# rtpi.net
KiCad netlist of a schematic drawn in Altium Designer
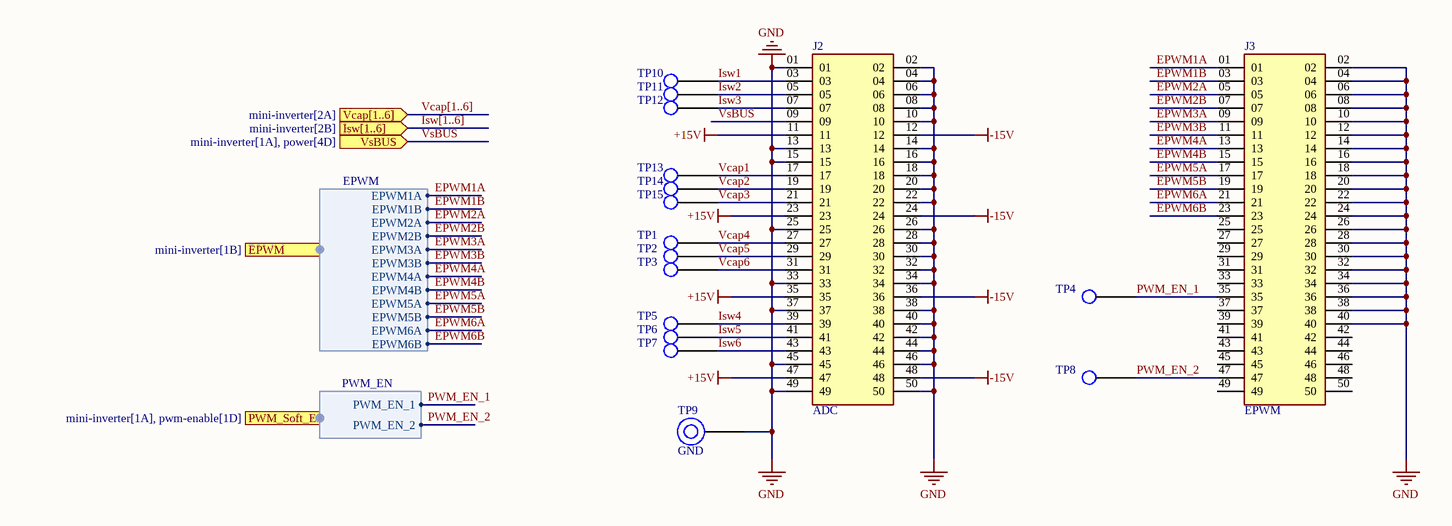
[diagram p0: rtpi.SchDoc]

(export (version "E")
  (design (tool "Eeschema 10.0.6"))
  (components
    (comp (ref "J2")
      (value "ADC")
      (footprint "SHF-125-01-L-D-RA")
      (description "50-Pin Simplus Connector")
      (fields (field (name "MP") "SHF-125-01-L-D-RA") (field (name "MF") "Samtec"))
      (libsource (lib "FYP_Components") (part "SHF-125-01-L-D-RA"))
    )
    (comp (ref "J3")
      (value "EPWM")
      (footprint "SHF-125-01-L-D-RA")
      (description "50-Pin Simplus Connector")
      (fields (field (name "MP") "SHF-125-01-L-D-RA") (field (name "MF") "Samtec"))
      (libsource (lib "FYP_Components") (part "SHF-125-01-L-D-RA"))
    )
    (comp (ref "TP1")
      (value "VC_1A")
      (footprint "PCB 1.32mm TestPoint")
      (description "20-313143 PCB Test Point, White, Through Hole Mount, 1.32 mm, Phosphor Bronze, Tin Plated Contacts")
      (libsource (lib "FYP_Components") (part "PCBTestpoint"))
    )
    (comp (ref "TP2")
      (value "VC_1B")
      (footprint "PCB 1.32mm TestPoint")
      (description "20-313143 PCB Test Point, White, Through Hole Mount, 1.32 mm, Phosphor Bronze, Tin Plated Contacts")
      (libsource (lib "FYP_Components") (part "PCBTestpoint"))
    )
    (comp (ref "TP3")
      (value "VC_1C")
      (footprint "PCB 1.32mm TestPoint")
      (description "20-313143 PCB Test Point, White, Through Hole Mount, 1.32 mm, Phosphor Bronze, Tin Plated Contacts")
      (libsource (lib "FYP_Components") (part "PCBTestpoint"))
    )
    (comp (ref "TP4")
      (value "PWMEN1")
      (footprint "PCB 1.32mm TestPoint")
      (description "20-313143 PCB Test Point, White, Through Hole Mount, 1.32 mm, Phosphor Bronze, Tin Plated Contacts")
      (libsource (lib "FYP_Components") (part "PCBTestpoint"))
    )
    (comp (ref "TP5")
      (value "I1")
      (footprint "PCB 1.32mm TestPoint")
      (description "20-313143 PCB Test Point, White, Through Hole Mount, 1.32 mm, Phosphor Bronze, Tin Plated Contacts")
      (libsource (lib "FYP_Components") (part "PCBTestpoint"))
    )
    (comp (ref "TP6")
      (value "I2")
      (footprint "PCB 1.32mm TestPoint")
      (description "20-313143 PCB Test Point, White, Through Hole Mount, 1.32 mm, Phosphor Bronze, Tin Plated Contacts")
      (libsource (lib "FYP_Components") (part "PCBTestpoint"))
    )
    (comp (ref "TP7")
      (value "I3")
      (footprint "PCB 1.32mm TestPoint")
      (description "20-313143 PCB Test Point, White, Through Hole Mount, 1.32 mm, Phosphor Bronze, Tin Plated Contacts")
      (libsource (lib "FYP_Components") (part "PCBTestpoint"))
    )
    (comp (ref "TP8")
      (value "PWMEN2")
      (footprint "PCB 1.32mm TestPoint")
      (description "20-313143 PCB Test Point, White, Through Hole Mount, 1.32 mm, Phosphor Bronze, Tin Plated Contacts")
      (libsource (lib "FYP_Components") (part "PCBTestpoint"))
    )
    (comp (ref "TP9")
      (value "GND")
      (footprint "1.9mm Hole")
      (description "H2182-01 PCB Test Point, PCB Mount, 1.9 mm, Brass, Tin Plated Contacts")
      (libsource (lib "FYP_Components") (part "GroundTestPoint"))
    )
    (comp (ref "TP10")
      (value "VC_1A")
      (footprint "PCB 1.32mm TestPoint")
      (description "20-313143 PCB Test Point, White, Through Hole Mount, 1.32 mm, Phosphor Bronze, Tin Plated Contacts")
      (libsource (lib "FYP_Components") (part "PCBTestpoint"))
    )
    (comp (ref "TP11")
      (value "VC_1B")
      (footprint "PCB 1.32mm TestPoint")
      (description "20-313143 PCB Test Point, White, Through Hole Mount, 1.32 mm, Phosphor Bronze, Tin Plated Contacts")
      (libsource (lib "FYP_Components") (part "PCBTestpoint"))
    )
    (comp (ref "TP12")
      (value "VC_1C")
      (footprint "PCB 1.32mm TestPoint")
      (description "20-313143 PCB Test Point, White, Through Hole Mount, 1.32 mm, Phosphor Bronze, Tin Plated Contacts")
      (libsource (lib "FYP_Components") (part "PCBTestpoint"))
    )
    (comp (ref "TP13")
      (value "VC_1A")
      (footprint "PCB 1.32mm TestPoint")
      (description "20-313143 PCB Test Point, White, Through Hole Mount, 1.32 mm, Phosphor Bronze, Tin Plated Contacts")
      (libsource (lib "FYP_Components") (part "PCBTestpoint"))
    )
    (comp (ref "TP14")
      (value "VC_1B")
      (footprint "PCB 1.32mm TestPoint")
      (description "20-313143 PCB Test Point, White, Through Hole Mount, 1.32 mm, Phosphor Bronze, Tin Plated Contacts")
      (libsource (lib "FYP_Components") (part "PCBTestpoint"))
    )
    (comp (ref "TP15")
      (value "VC_1C")
      (footprint "PCB 1.32mm TestPoint")
      (description "20-313143 PCB Test Point, White, Through Hole Mount, 1.32 mm, Phosphor Bronze, Tin Plated Contacts")
      (libsource (lib "FYP_Components") (part "PCBTestpoint"))
    )
  )
  (nets
    (net (code "3") (name "+15V") (class "Default")
      (node (ref "J2") (pin "11") (pinfunction "11_11") (pintype "passive"))
      (node (ref "J2") (pin "23") (pinfunction "23_23") (pintype "passive"))
      (node (ref "J2") (pin "35") (pinfunction "35_35") (pintype "passive"))
      (node (ref "J2") (pin "47") (pinfunction "47_47") (pintype "passive"))
    )
    (net (code "4") (name "-15V") (class "Default")
      (node (ref "J2") (pin "12") (pinfunction "12_12") (pintype "passive"))
      (node (ref "J2") (pin "24") (pinfunction "24_24") (pintype "passive"))
      (node (ref "J2") (pin "36") (pinfunction "36_36") (pintype "passive"))
      (node (ref "J2") (pin "48") (pinfunction "48_48") (pintype "passive"))
    )
    (net (code "5") (name "/EPWM1A") (class "Default")
      (node (ref "J3") (pin "01") (pinfunction "01_01") (pintype "passive"))
    )
    (net (code "6") (name "/EPWM1B") (class "Default")
      (node (ref "J3") (pin "03") (pinfunction "03_03") (pintype "passive"))
    )
    (net (code "7") (name "/EPWM2A") (class "Default")
      (node (ref "J3") (pin "05") (pinfunction "05_05") (pintype "passive"))
    )
    (net (code "8") (name "/EPWM2B") (class "Default")
      (node (ref "J3") (pin "07") (pinfunction "07_07") (pintype "passive"))
    )
    (net (code "9") (name "/EPWM3A") (class "Default")
      (node (ref "J3") (pin "09") (pinfunction "09_09") (pintype "passive"))
    )
    (net (code "10") (name "/EPWM3B") (class "Default")
      (node (ref "J3") (pin "11") (pinfunction "11_11") (pintype "passive"))
    )
    (net (code "11") (name "/EPWM4A") (class "Default")
      (node (ref "J3") (pin "13") (pinfunction "13_13") (pintype "passive"))
    )
    (net (code "12") (name "/EPWM4B") (class "Default")
      (node (ref "J3") (pin "15") (pinfunction "15_15") (pintype "passive"))
    )
    (net (code "13") (name "/EPWM5A") (class "Default")
      (node (ref "J3") (pin "17") (pinfunction "17_17") (pintype "passive"))
    )
    (net (code "14") (name "/EPWM5B") (class "Default")
      (node (ref "J3") (pin "19") (pinfunction "19_19") (pintype "passive"))
    )
    (net (code "15") (name "/EPWM6A") (class "Default")
      (node (ref "J3") (pin "21") (pinfunction "21_21") (pintype "passive"))
    )
    (net (code "16") (name "/EPWM6B") (class "Default")
      (node (ref "J3") (pin "23") (pinfunction "23_23") (pintype "passive"))
    )
    (net (code "17") (name "/Isw1") (class "Default")
      (node (ref "J2") (pin "03") (pinfunction "03_03") (pintype "passive"))
      (node (ref "TP10") (pin "1") (pinfunction "1_1") (pintype "passive"))
    )
    (net (code "18") (name "/Isw2") (class "Default")
      (node (ref "J2") (pin "05") (pinfunction "05_05") (pintype "passive"))
      (node (ref "TP11") (pin "1") (pinfunction "1_1") (pintype "passive"))
    )
    (net (code "19") (name "/Isw3") (class "Default")
      (node (ref "J2") (pin "07") (pinfunction "07_07") (pintype "passive"))
      (node (ref "TP12") (pin "1") (pinfunction "1_1") (pintype "passive"))
    )
    (net (code "20") (name "/Isw4") (class "Default")
      (node (ref "J2") (pin "39") (pinfunction "39_39") (pintype "passive"))
      (node (ref "TP5") (pin "1") (pinfunction "1_1") (pintype "passive"))
    )
    (net (code "21") (name "/Isw5") (class "Default")
      (node (ref "J2") (pin "41") (pinfunction "41_41") (pintype "passive"))
      (node (ref "TP6") (pin "1") (pinfunction "1_1") (pintype "passive"))
    )
    (net (code "22") (name "/Isw6") (class "Default")
      (node (ref "J2") (pin "43") (pinfunction "43_43") (pintype "passive"))
      (node (ref "TP7") (pin "1") (pinfunction "1_1") (pintype "passive"))
    )
    (net (code "24") (name "/PWM_EN_1") (class "Default")
      (node (ref "J3") (pin "35") (pinfunction "35_35") (pintype "passive"))
      (node (ref "TP4") (pin "1") (pinfunction "1_1") (pintype "passive"))
    )
    (net (code "25") (name "/PWM_EN_2") (class "Default")
      (node (ref "J3") (pin "47") (pinfunction "47_47") (pintype "passive"))
      (node (ref "TP8") (pin "1") (pinfunction "1_1") (pintype "passive"))
    )
    (net (code "26") (name "/Vcap1") (class "Default")
      (node (ref "J2") (pin "17") (pinfunction "17_17") (pintype "passive"))
      (node (ref "TP13") (pin "1") (pinfunction "1_1") (pintype "passive"))
    )
    (net (code "27") (name "/Vcap2") (class "Default")
      (node (ref "J2") (pin "19") (pinfunction "19_19") (pintype "passive"))
      (node (ref "TP14") (pin "1") (pinfunction "1_1") (pintype "passive"))
    )
    (net (code "28") (name "/Vcap3") (class "Default")
      (node (ref "J2") (pin "21") (pinfunction "21_21") (pintype "passive"))
      (node (ref "TP15") (pin "1") (pinfunction "1_1") (pintype "passive"))
    )
    (net (code "29") (name "/Vcap4") (class "Default")
      (node (ref "J2") (pin "27") (pinfunction "27_27") (pintype "passive"))
      (node (ref "TP1") (pin "1") (pinfunction "1_1") (pintype "passive"))
    )
    (net (code "30") (name "/Vcap5") (class "Default")
      (node (ref "J2") (pin "29") (pinfunction "29_29") (pintype "passive"))
      (node (ref "TP2") (pin "1") (pinfunction "1_1") (pintype "passive"))
    )
    (net (code "31") (name "/Vcap6") (class "Default")
      (node (ref "J2") (pin "31") (pinfunction "31_31") (pintype "passive"))
      (node (ref "TP3") (pin "1") (pinfunction "1_1") (pintype "passive"))
    )
    (net (code "33") (name "/VsBUS") (class "Default")
      (node (ref "J2") (pin "09") (pinfunction "09_09") (pintype "passive"))
    )
    (net (code "36") (name "GND") (class "Default")
      (node (ref "J2") (pin "01") (pinfunction "01_01") (pintype "passive"))
      (node (ref "J2") (pin "02") (pinfunction "02_02") (pintype "passive"))
      (node (ref "J2") (pin "04") (pinfunction "04_04") (pintype "passive"))
      (node (ref "J2") (pin "06") (pinfunction "06_06") (pintype "passive"))
      (node (ref "J2") (pin "08") (pinfunction "08_08") (pintype "passive"))
      (node (ref "J2") (pin "10") (pinfunction "10_10") (pintype "passive"))
      (node (ref "J2") (pin "13") (pinfunction "13_13") (pintype "passive"))
      (node (ref "J2") (pin "14") (pinfunction "14_14") (pintype "passive"))
      (node (ref "J2") (pin "15") (pinfunction "15_15") (pintype "passive"))
      (node (ref "J2") (pin "16") (pinfunction "16_16") (pintype "passive"))
      (node (ref "J2") (pin "18") (pinfunction "18_18") (pintype "passive"))
      (node (ref "J2") (pin "20") (pinfunction "20_20") (pintype "passive"))
      (node (ref "J2") (pin "22") (pinfunction "22_22") (pintype "passive"))
      (node (ref "J2") (pin "25") (pinfunction "25_25") (pintype "passive"))
      (node (ref "J2") (pin "26") (pinfunction "26_26") (pintype "passive"))
      (node (ref "J2") (pin "28") (pinfunction "28_28") (pintype "passive"))
      (node (ref "J2") (pin "30") (pinfunction "30_30") (pintype "passive"))
      (node (ref "J2") (pin "32") (pinfunction "32_32") (pintype "passive"))
      (node (ref "J2") (pin "33") (pinfunction "33_33") (pintype "passive"))
      (node (ref "J2") (pin "34") (pinfunction "34_34") (pintype "passive"))
      (node (ref "J2") (pin "37") (pinfunction "37_37") (pintype "passive"))
      (node (ref "J2") (pin "38") (pinfunction "38_38") (pintype "passive"))
      (node (ref "J2") (pin "40") (pinfunction "40_40") (pintype "passive"))
      (node (ref "J2") (pin "42") (pinfunction "42_42") (pintype "passive"))
      (node (ref "J2") (pin "44") (pinfunction "44_44") (pintype "passive"))
      (node (ref "J2") (pin "45") (pinfunction "45_45") (pintype "passive"))
      (node (ref "J2") (pin "46") (pinfunction "46_46") (pintype "passive"))
      (node (ref "J2") (pin "49") (pinfunction "49_49") (pintype "passive"))
      (node (ref "J2") (pin "50") (pinfunction "50_50") (pintype "passive"))
      (node (ref "J3") (pin "02") (pinfunction "02_02") (pintype "passive"))
      (node (ref "J3") (pin "04") (pinfunction "04_04") (pintype "passive"))
      (node (ref "J3") (pin "06") (pinfunction "06_06") (pintype "passive"))
      (node (ref "J3") (pin "08") (pinfunction "08_08") (pintype "passive"))
      (node (ref "J3") (pin "10") (pinfunction "10_10") (pintype "passive"))
      (node (ref "J3") (pin "12") (pinfunction "12_12") (pintype "passive"))
      (node (ref "J3") (pin "14") (pinfunction "14_14") (pintype "passive"))
      (node (ref "J3") (pin "16") (pinfunction "16_16") (pintype "passive"))
      (node (ref "J3") (pin "18") (pinfunction "18_18") (pintype "passive"))
      (node (ref "J3") (pin "20") (pinfunction "20_20") (pintype "passive"))
      (node (ref "J3") (pin "22") (pinfunction "22_22") (pintype "passive"))
      (node (ref "J3") (pin "24") (pinfunction "24_24") (pintype "passive"))
      (node (ref "J3") (pin "26") (pinfunction "26_26") (pintype "passive"))
      (node (ref "J3") (pin "28") (pinfunction "28_28") (pintype "passive"))
      (node (ref "J3") (pin "30") (pinfunction "30_30") (pintype "passive"))
      (node (ref "J3") (pin "32") (pinfunction "32_32") (pintype "passive"))
      (node (ref "J3") (pin "34") (pinfunction "34_34") (pintype "passive"))
      (node (ref "J3") (pin "36") (pinfunction "36_36") (pintype "passive"))
      (node (ref "J3") (pin "38") (pinfunction "38_38") (pintype "passive"))
      (node (ref "J3") (pin "40") (pinfunction "40_40") (pintype "passive"))
      (node (ref "TP9") (pin "1") (pinfunction "1_1") (pintype "passive"))
    )
    (net (code "37") (name "unconnected-(J3-Pad25)") (class "Default")
      (node (ref "J3") (pin "25") (pinfunction "25_25") (pintype "passive"))
    )
    (net (code "38") (name "unconnected-(J3-Pad27)") (class "Default")
      (node (ref "J3") (pin "27") (pinfunction "27_27") (pintype "passive"))
    )
    (net (code "39") (name "unconnected-(J3-Pad29)") (class "Default")
      (node (ref "J3") (pin "29") (pinfunction "29_29") (pintype "passive"))
    )
    (net (code "40") (name "unconnected-(J3-Pad31)") (class "Default")
      (node (ref "J3") (pin "31") (pinfunction "31_31") (pintype "passive"))
    )
    (net (code "41") (name "unconnected-(J3-Pad33)") (class "Default")
      (node (ref "J3") (pin "33") (pinfunction "33_33") (pintype "passive"))
    )
    (net (code "42") (name "unconnected-(J3-Pad37)") (class "Default")
      (node (ref "J3") (pin "37") (pinfunction "37_37") (pintype "passive"))
    )
    (net (code "43") (name "unconnected-(J3-Pad39)") (class "Default")
      (node (ref "J3") (pin "39") (pinfunction "39_39") (pintype "passive"))
    )
    (net (code "44") (name "unconnected-(J3-Pad41)") (class "Default")
      (node (ref "J3") (pin "41") (pinfunction "41_41") (pintype "passive"))
    )
    (net (code "45") (name "unconnected-(J3-Pad42)") (class "Default")
      (node (ref "J3") (pin "42") (pinfunction "42_42") (pintype "passive"))
    )
    (net (code "46") (name "unconnected-(J3-Pad43)") (class "Default")
      (node (ref "J3") (pin "43") (pinfunction "43_43") (pintype "passive"))
    )
    (net (code "47") (name "unconnected-(J3-Pad44)") (class "Default")
      (node (ref "J3") (pin "44") (pinfunction "44_44") (pintype "passive"))
    )
    (net (code "48") (name "unconnected-(J3-Pad45)") (class "Default")
      (node (ref "J3") (pin "45") (pinfunction "45_45") (pintype "passive"))
    )
    (net (code "49") (name "unconnected-(J3-Pad46)") (class "Default")
      (node (ref "J3") (pin "46") (pinfunction "46_46") (pintype "passive"))
    )
    (net (code "50") (name "unconnected-(J3-Pad48)") (class "Default")
      (node (ref "J3") (pin "48") (pinfunction "48_48") (pintype "passive"))
    )
    (net (code "51") (name "unconnected-(J3-Pad49)") (class "Default")
      (node (ref "J3") (pin "49") (pinfunction "49_49") (pintype "passive"))
    )
    (net (code "52") (name "unconnected-(J3-Pad50)") (class "Default")
      (node (ref "J3") (pin "50") (pinfunction "50_50") (pintype "passive"))
    )
  )
)
